# encoder-tester.net
KiCad netlist of a schematic drawn in EAGLE
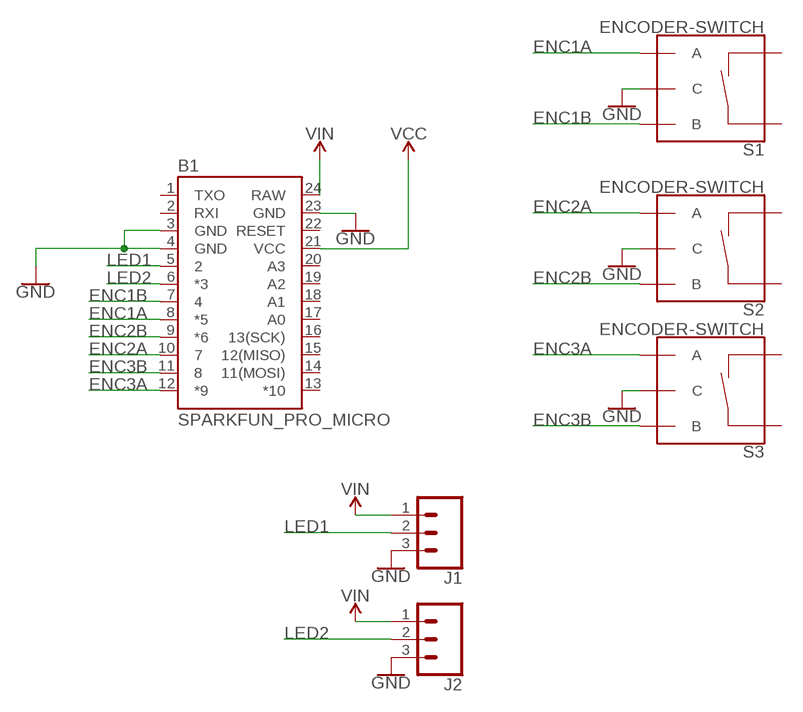
[diagram p0: schematic, sheet 1]

(export (version "E")
  (design (tool "Eeschema 10.0.6"))
  (components
    (comp (ref "B1")
      (value "SPARKFUN_PRO_MICRO")
      (footprint "eagle-import:SPARKFUN_PRO_MICRO")
      (libsource (lib "eagle-import") (part "SPARKFUN_PRO_MICRO"))
    )
    (comp (ref "J1")
      (value "CONN_03")
      (footprint "eagle-import:1X03")
      (libsource (lib "eagle-import") (part "CONN_03"))
    )
    (comp (ref "J2")
      (value "CONN_03")
      (footprint "eagle-import:1X03")
      (libsource (lib "eagle-import") (part "CONN_03"))
    )
    (comp (ref "S1")
      (value "ENCODER-SWITCH")
      (footprint "eagle-import:ROTARY_ENC_PLAIN")
      (libsource (lib "eagle-import") (part "ENCODER-SWITCH"))
    )
    (comp (ref "S2")
      (value "ENCODER-SWITCH")
      (footprint "eagle-import:ROTARY_ENC_PLAIN")
      (libsource (lib "eagle-import") (part "ENCODER-SWITCH"))
    )
    (comp (ref "S3")
      (value "ENCODER-SWITCH")
      (footprint "eagle-import:ROTARY_ENC_PLAIN")
      (libsource (lib "eagle-import") (part "ENCODER-SWITCH"))
    )
  )
  (nets
    (net (code "1") (name "/ENC1A") (class "Default")
      (node (ref "B1") (pin "8") (pinfunction "*5_8") (pintype "bidirectional"))
      (node (ref "S1") (pin "A") (pinfunction "A_A") (pintype "bidirectional"))
    )
    (net (code "2") (name "/ENC1B") (class "Default")
      (node (ref "B1") (pin "7") (pinfunction "4_7") (pintype "bidirectional"))
      (node (ref "S1") (pin "B") (pinfunction "B_B") (pintype "bidirectional"))
    )
    (net (code "3") (name "/ENC2A") (class "Default")
      (node (ref "B1") (pin "10") (pinfunction "7_10") (pintype "bidirectional"))
      (node (ref "S2") (pin "A") (pinfunction "A_A") (pintype "bidirectional"))
    )
    (net (code "4") (name "/ENC2B") (class "Default")
      (node (ref "B1") (pin "9") (pinfunction "*6_9") (pintype "bidirectional"))
      (node (ref "S2") (pin "B") (pinfunction "B_B") (pintype "bidirectional"))
    )
    (net (code "5") (name "/ENC3A") (class "Default")
      (node (ref "B1") (pin "12") (pinfunction "*9_12") (pintype "bidirectional"))
      (node (ref "S3") (pin "A") (pinfunction "A_A") (pintype "bidirectional"))
    )
    (net (code "6") (name "/ENC3B") (class "Default")
      (node (ref "B1") (pin "11") (pinfunction "8_11") (pintype "bidirectional"))
      (node (ref "S3") (pin "B") (pinfunction "B_B") (pintype "bidirectional"))
    )
    (net (code "7") (name "/LED1") (class "Default")
      (node (ref "B1") (pin "5") (pinfunction "2_5") (pintype "bidirectional"))
      (node (ref "J1") (pin "2") (pinfunction "2_2") (pintype "passive"))
    )
    (net (code "8") (name "/LED2") (class "Default")
      (node (ref "B1") (pin "6") (pinfunction "*3_6") (pintype "bidirectional"))
      (node (ref "J2") (pin "2") (pinfunction "2_2") (pintype "passive"))
    )
    (net (code "9") (name "GND") (class "Default")
      (node (ref "B1") (pin "23") (pinfunction "GND_23") (pintype "power_in"))
      (node (ref "B1") (pin "3") (pinfunction "GND_3") (pintype "power_in"))
      (node (ref "B1") (pin "4") (pinfunction "GND_4") (pintype "power_in"))
      (node (ref "J1") (pin "3") (pinfunction "3_3") (pintype "passive"))
      (node (ref "J2") (pin "3") (pinfunction "3_3") (pintype "passive"))
      (node (ref "S1") (pin "C") (pinfunction "C_C") (pintype "bidirectional"))
      (node (ref "S2") (pin "C") (pinfunction "C_C") (pintype "bidirectional"))
      (node (ref "S3") (pin "C") (pinfunction "C_C") (pintype "bidirectional"))
    )
    (net (code "10") (name "VCC") (class "Default")
      (node (ref "B1") (pin "21") (pinfunction "VCC_21") (pintype "power_in"))
    )
    (net (code "11") (name "VIN") (class "Default")
      (node (ref "B1") (pin "24") (pinfunction "RAW_24") (pintype "power_in"))
      (node (ref "J1") (pin "1") (pinfunction "1_1") (pintype "passive"))
      (node (ref "J2") (pin "1") (pinfunction "1_1") (pintype "passive"))
    )
    (net (code "12") (name "unconnected-(B1-*10-Pad13)") (class "Default")
      (node (ref "B1") (pin "13") (pinfunction "*10_13") (pintype "bidirectional"))
    )
    (net (code "13") (name "unconnected-(B1-11(MOSI)-Pad14)") (class "Default")
      (node (ref "B1") (pin "14") (pinfunction "11(MOSI)_14") (pintype "bidirectional"))
    )
    (net (code "14") (name "unconnected-(B1-12(MISO)-Pad15)") (class "Default")
      (node (ref "B1") (pin "15") (pinfunction "12(MISO)_15") (pintype "bidirectional"))
    )
    (net (code "15") (name "unconnected-(B1-13(SCK)-Pad16)") (class "Default")
      (node (ref "B1") (pin "16") (pinfunction "13(SCK)_16") (pintype "bidirectional"))
    )
    (net (code "16") (name "unconnected-(B1-A0-Pad17)") (class "Default")
      (node (ref "B1") (pin "17") (pinfunction "A0_17") (pintype "bidirectional"))
    )
    (net (code "17") (name "unconnected-(B1-A1-Pad18)") (class "Default")
      (node (ref "B1") (pin "18") (pinfunction "A1_18") (pintype "bidirectional"))
    )
    (net (code "18") (name "unconnected-(B1-A2-Pad19)") (class "Default")
      (node (ref "B1") (pin "19") (pinfunction "A2_19") (pintype "bidirectional"))
    )
    (net (code "19") (name "unconnected-(B1-A3-Pad20)") (class "Default")
      (node (ref "B1") (pin "20") (pinfunction "A3_20") (pintype "bidirectional"))
    )
    (net (code "20") (name "unconnected-(B1-RESET-Pad22)") (class "Default")
      (node (ref "B1") (pin "22") (pinfunction "RESET_22") (pintype "bidirectional"))
    )
    (net (code "21") (name "unconnected-(B1-RXI-Pad2)") (class "Default")
      (node (ref "B1") (pin "2") (pinfunction "RXI_2") (pintype "bidirectional"))
    )
    (net (code "22") (name "unconnected-(B1-TXO-Pad1)") (class "Default")
      (node (ref "B1") (pin "1") (pinfunction "TXO_1") (pintype "bidirectional"))
    )
    (net (code "23") (name "unconnected-(S1-PadSW+)") (class "Default")
      (node (ref "S1") (pin "SW+") (pinfunction "SW+_SW+") (pintype "bidirectional"))
    )
    (net (code "24") (name "unconnected-(S1-PadSW-)") (class "Default")
      (node (ref "S1") (pin "SW-") (pinfunction "SW-_SW-") (pintype "bidirectional"))
    )
    (net (code "25") (name "unconnected-(S2-PadSW+)") (class "Default")
      (node (ref "S2") (pin "SW+") (pinfunction "SW+_SW+") (pintype "bidirectional"))
    )
    (net (code "26") (name "unconnected-(S2-PadSW-)") (class "Default")
      (node (ref "S2") (pin "SW-") (pinfunction "SW-_SW-") (pintype "bidirectional"))
    )
    (net (code "27") (name "unconnected-(S3-PadSW+)") (class "Default")
      (node (ref "S3") (pin "SW+") (pinfunction "SW+_SW+") (pintype "bidirectional"))
    )
    (net (code "28") (name "unconnected-(S3-PadSW-)") (class "Default")
      (node (ref "S3") (pin "SW-") (pinfunction "SW-_SW-") (pintype "bidirectional"))
    )
  )
)
